# JFET_S_R.net
KiCad netlist of a schematic drawn in EAGLE
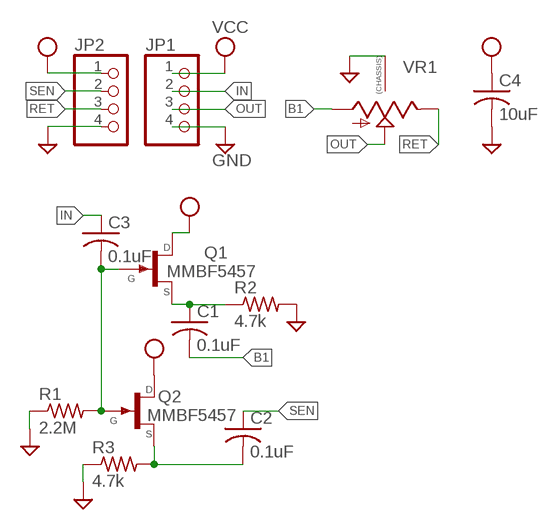
[diagram p0: schematic, sheet 1]

(export (version "E")
  (design (tool "Eeschema 10.0.6"))
  (components
    (comp (ref "C1")
      (value "0.1uF")
      (footprint "eagle-import:C0402")
      (libsource (lib "eagle-import") (part "C-USC0402"))
    )
    (comp (ref "C2")
      (value "0.1uF")
      (footprint "eagle-import:C0402")
      (libsource (lib "eagle-import") (part "C-USC0402"))
    )
    (comp (ref "C3")
      (value "0.1uF")
      (footprint "eagle-import:C0402")
      (libsource (lib "eagle-import") (part "C-USC0402"))
    )
    (comp (ref "C4")
      (value "10uF")
      (footprint "eagle-import:C0805")
      (libsource (lib "eagle-import") (part "C-USC0805"))
    )
    (comp (ref "JP1")
      (value "PINHD-1X4")
      (footprint "eagle-import:1X04")
      (libsource (lib "eagle-import") (part "PINHD-1X4"))
    )
    (comp (ref "JP2")
      (value "PINHD-1X4")
      (footprint "eagle-import:1X04")
      (libsource (lib "eagle-import") (part "PINHD-1X4"))
    )
    (comp (ref "Q1")
      (value "MMBF5457")
      (footprint "eagle-import:SOT23")
      (fields (field (name "MF") "ON Semiconductor"))
      (libsource (lib "eagle-import") (part "MMBF5457"))
    )
    (comp (ref "Q2")
      (value "MMBF5457")
      (footprint "eagle-import:SOT23")
      (fields (field (name "MF") "ON Semiconductor"))
      (libsource (lib "eagle-import") (part "MMBF5457"))
    )
    (comp (ref "R1")
      (value "2.2M")
      (footprint "eagle-import:R0402")
      (libsource (lib "eagle-import") (part "R-US_R0402"))
    )
    (comp (ref "R2")
      (value "4.7k")
      (footprint "eagle-import:R0402")
      (libsource (lib "eagle-import") (part "R-US_R0402"))
    )
    (comp (ref "R3")
      (value "4.7k")
      (footprint "eagle-import:R0402")
      (libsource (lib "eagle-import") (part "R-US_R0402"))
    )
    (comp (ref "VR1")
      (value "9MM_SNAP-IN_POT_CHASSIS")
      (footprint "eagle-import:9MM_SNAP-IN_POT")
      (libsource (lib "eagle-import") (part "9MM_SNAP-IN_POT_CHASSIS"))
    )
  )
  (nets
    (net (code "1") (name "B1") (class "Default")
      (node (ref "C1") (pin "2") (pinfunction "2_2") (pintype "passive"))
      (node (ref "VR1") (pin "1") (pinfunction "A_1") (pintype "passive"))
    )
    (net (code "2") (name "GND") (class "Default")
      (node (ref "C4") (pin "2") (pinfunction "2_2") (pintype "passive"))
      (node (ref "JP1") (pin "4") (pinfunction "4_4") (pintype "passive"))
      (node (ref "JP2") (pin "4") (pinfunction "4_4") (pintype "passive"))
      (node (ref "R1") (pin "1") (pinfunction "1_1") (pintype "passive"))
      (node (ref "R2") (pin "2") (pinfunction "2_2") (pintype "passive"))
      (node (ref "R3") (pin "1") (pinfunction "1_1") (pintype "passive"))
      (node (ref "VR1") (pin "CHASSIS1") (pinfunction "P$1_CHASSIS1") (pintype "passive"))
      (node (ref "VR1") (pin "CHASSIS2") (pinfunction "P$1_CHASSIS2") (pintype "passive"))
    )
    (net (code "3") (name "IN") (class "Default")
      (node (ref "C3") (pin "1") (pinfunction "1_1") (pintype "passive"))
      (node (ref "JP1") (pin "2") (pinfunction "2_2") (pintype "passive"))
    )
    (net (code "4") (name "Net-(Q1-G)") (class "Default")
      (node (ref "C3") (pin "2") (pinfunction "2_2") (pintype "passive"))
      (node (ref "Q1") (pin "3") (pinfunction "G_3") (pintype "passive"))
      (node (ref "Q2") (pin "3") (pinfunction "G_3") (pintype "passive"))
      (node (ref "R1") (pin "2") (pinfunction "2_2") (pintype "passive"))
    )
    (net (code "5") (name "Net-(Q1-S)") (class "Default")
      (node (ref "C1") (pin "1") (pinfunction "1_1") (pintype "passive"))
      (node (ref "Q1") (pin "2") (pinfunction "S_2") (pintype "passive"))
      (node (ref "R2") (pin "1") (pinfunction "1_1") (pintype "passive"))
    )
    (net (code "6") (name "Net-(Q2-S)") (class "Default")
      (node (ref "C2") (pin "2") (pinfunction "2_2") (pintype "passive"))
      (node (ref "Q2") (pin "2") (pinfunction "S_2") (pintype "passive"))
      (node (ref "R3") (pin "2") (pinfunction "2_2") (pintype "passive"))
    )
    (net (code "7") (name "OUT") (class "Default")
      (node (ref "JP1") (pin "3") (pinfunction "3_3") (pintype "passive"))
      (node (ref "VR1") (pin "2") (pinfunction "S_2") (pintype "passive"))
    )
    (net (code "8") (name "RET") (class "Default")
      (node (ref "JP2") (pin "3") (pinfunction "3_3") (pintype "passive"))
      (node (ref "VR1") (pin "3") (pinfunction "E_3") (pintype "passive"))
    )
    (net (code "9") (name "SEN") (class "Default")
      (node (ref "C2") (pin "1") (pinfunction "1_1") (pintype "passive"))
      (node (ref "JP2") (pin "2") (pinfunction "2_2") (pintype "passive"))
    )
    (net (code "10") (name "VCC") (class "Default")
      (node (ref "C4") (pin "1") (pinfunction "1_1") (pintype "passive"))
      (node (ref "JP1") (pin "1") (pinfunction "1_1") (pintype "passive"))
      (node (ref "JP2") (pin "1") (pinfunction "1_1") (pintype "passive"))
      (node (ref "Q1") (pin "1") (pinfunction "D_1") (pintype "passive"))
      (node (ref "Q2") (pin "1") (pinfunction "D_1") (pintype "passive"))
    )
  )
)
